# lupa300v3.net
KiCad netlist of a schematic drawn in EAGLE
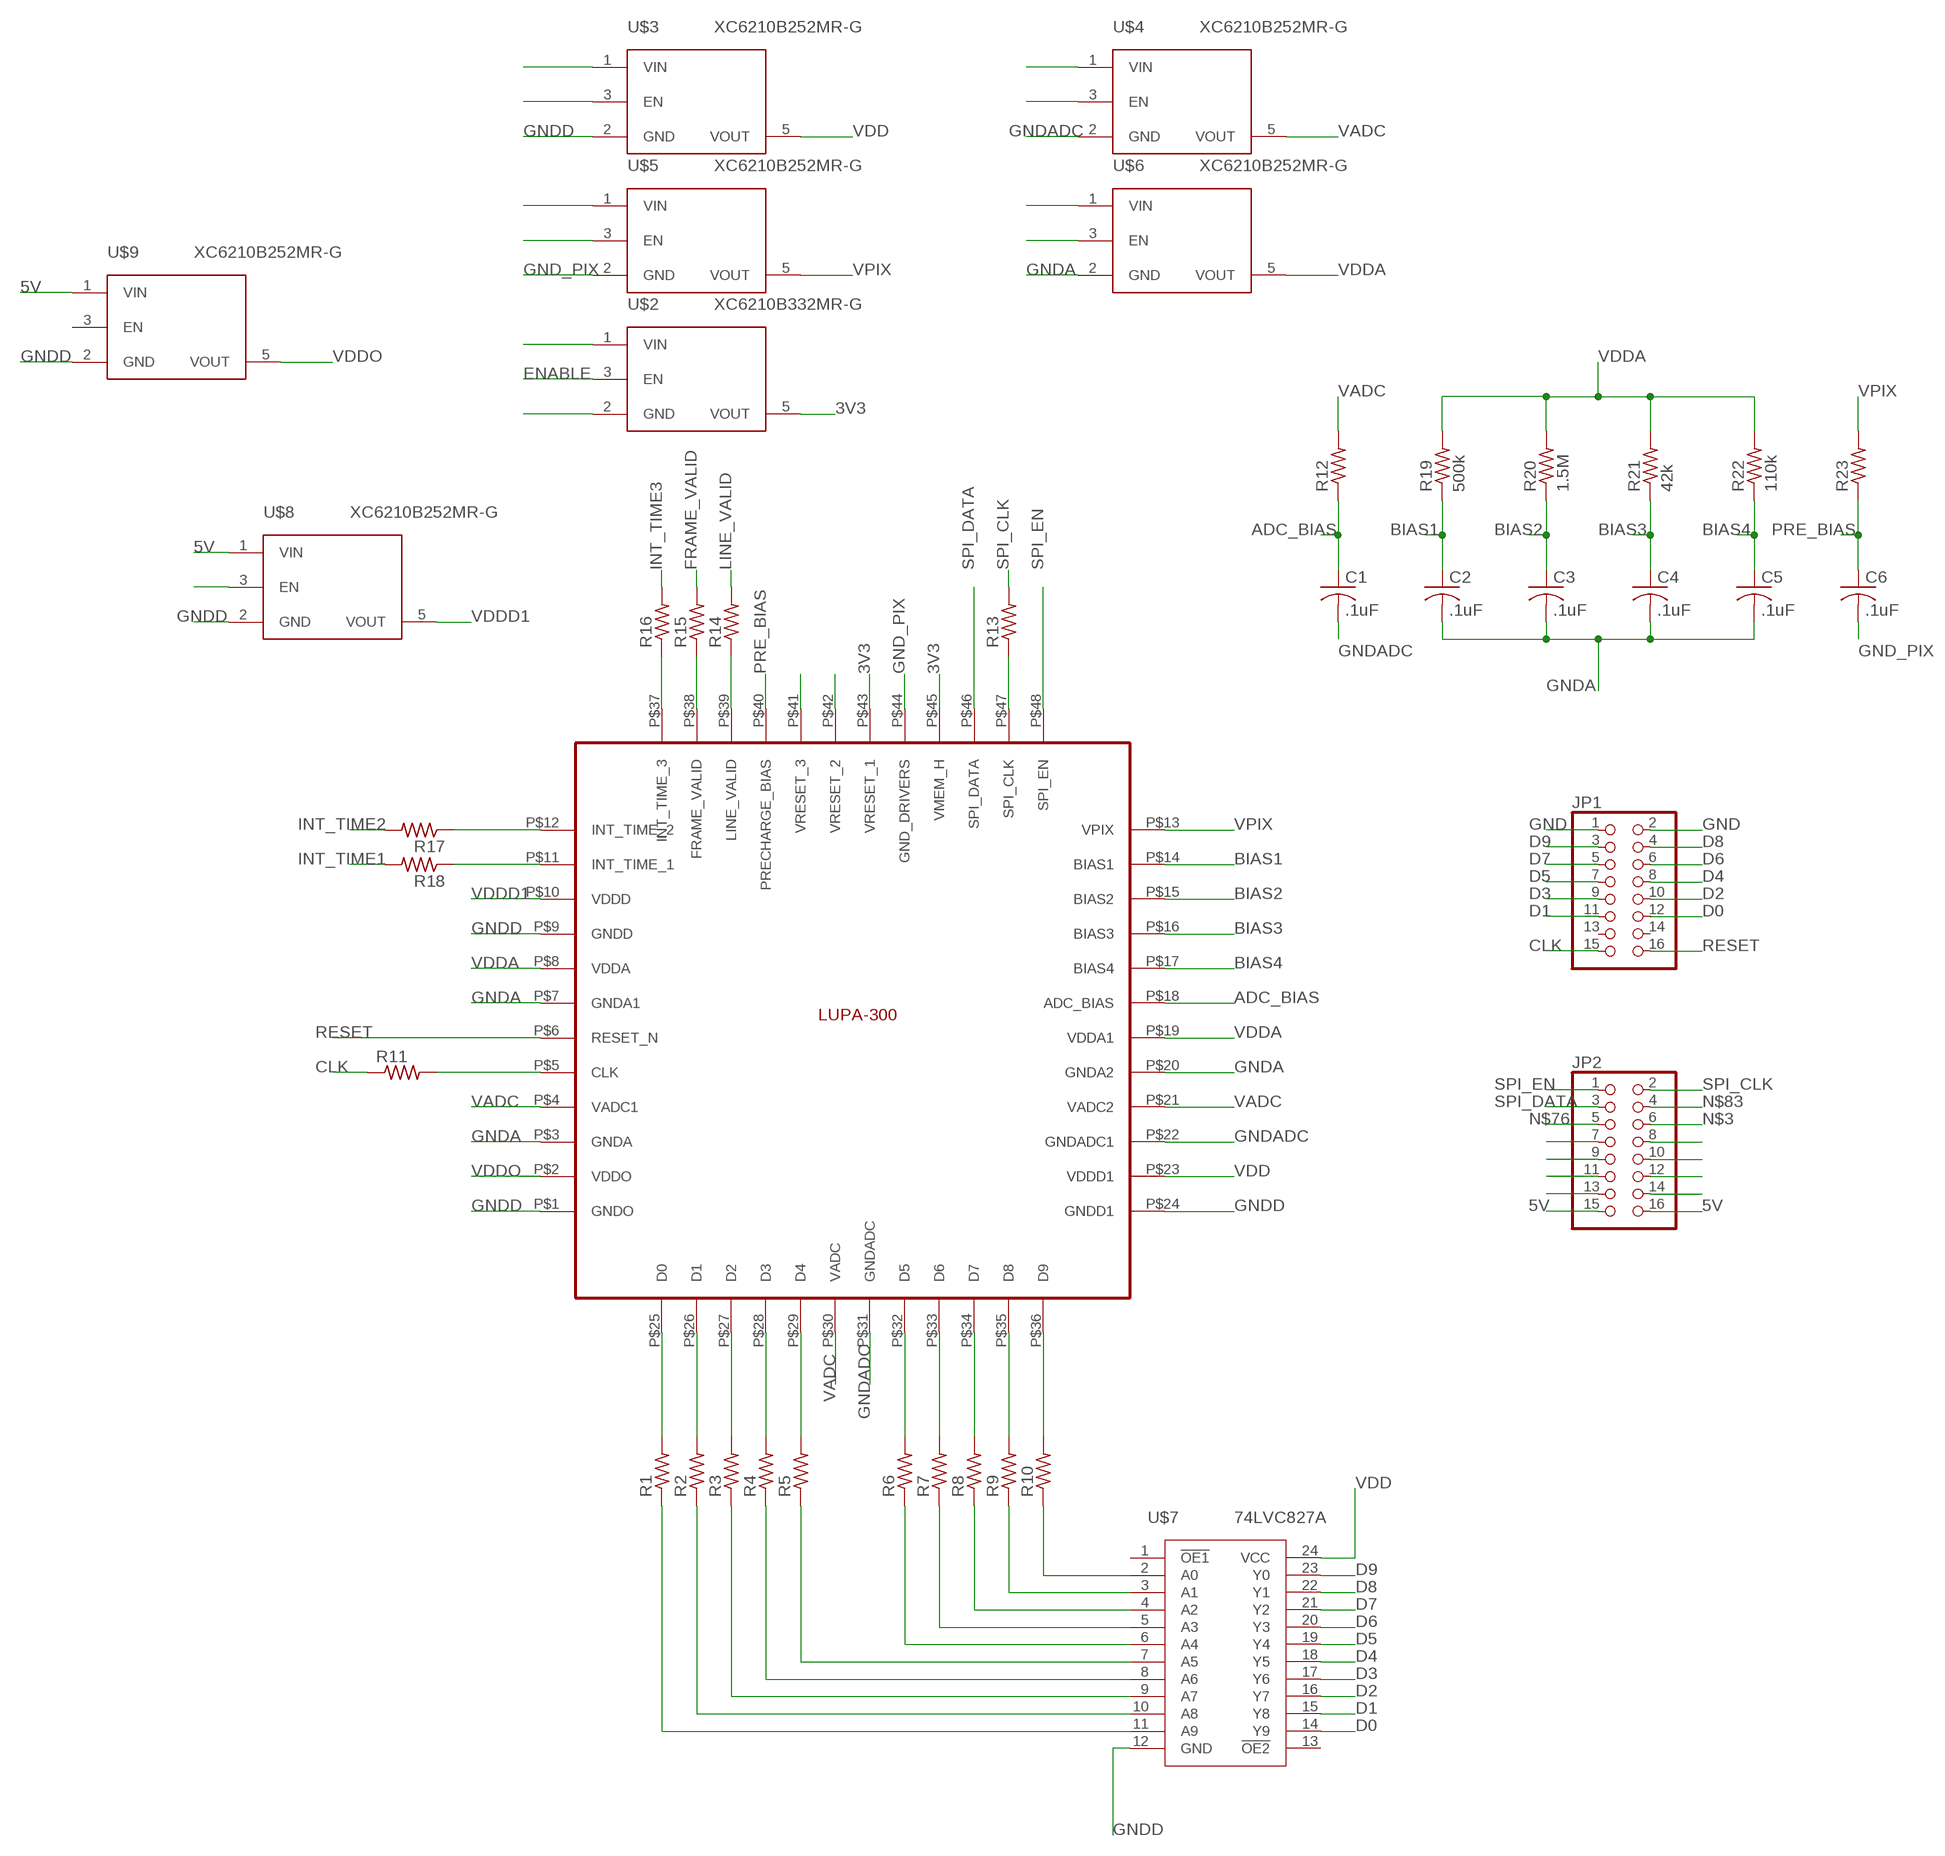
[diagram p0: schematic, sheet 1]

(export (version "E")
  (design (tool "Eeschema 10.0.6"))
  (components
    (comp (ref "C1")
      (value ".1uF")
      (footprint "eagle-import:C0603K")
      (libsource (lib "eagle-import") (part "C-USC0603K"))
    )
    (comp (ref "C2")
      (value ".1uF")
      (footprint "eagle-import:C0603K")
      (libsource (lib "eagle-import") (part "C-USC0603K"))
    )
    (comp (ref "C3")
      (value ".1uF")
      (footprint "eagle-import:C0603K")
      (libsource (lib "eagle-import") (part "C-USC0603K"))
    )
    (comp (ref "C4")
      (value ".1uF")
      (footprint "eagle-import:C0603K")
      (libsource (lib "eagle-import") (part "C-USC0603K"))
    )
    (comp (ref "C5")
      (value ".1uF")
      (footprint "eagle-import:C0603K")
      (libsource (lib "eagle-import") (part "C-USC0603K"))
    )
    (comp (ref "C6")
      (value ".1uF")
      (footprint "eagle-import:C0603K")
      (libsource (lib "eagle-import") (part "C-USC0603K"))
    )
    (comp (ref "JP1")
      (value "PINHD-2X8")
      (footprint "eagle-import:2X08")
      (libsource (lib "eagle-import") (part "PINHD-2X8"))
    )
    (comp (ref "JP2")
      (value "PINHD-2X8")
      (footprint "eagle-import:2X08")
      (libsource (lib "eagle-import") (part "PINHD-2X8"))
    )
    (comp (ref "R1")
      (value "R-US_R0603")
      (footprint "eagle-import:R0603")
      (libsource (lib "eagle-import") (part "R-US_R0603"))
    )
    (comp (ref "R2")
      (value "R-US_R0603")
      (footprint "eagle-import:R0603")
      (libsource (lib "eagle-import") (part "R-US_R0603"))
    )
    (comp (ref "R3")
      (value "R-US_R0603")
      (footprint "eagle-import:R0603")
      (libsource (lib "eagle-import") (part "R-US_R0603"))
    )
    (comp (ref "R4")
      (value "R-US_R0603")
      (footprint "eagle-import:R0603")
      (libsource (lib "eagle-import") (part "R-US_R0603"))
    )
    (comp (ref "R5")
      (value "R-US_R0603")
      (footprint "eagle-import:R0603")
      (libsource (lib "eagle-import") (part "R-US_R0603"))
    )
    (comp (ref "R6")
      (value "R-US_R0603")
      (footprint "eagle-import:R0603")
      (libsource (lib "eagle-import") (part "R-US_R0603"))
    )
    (comp (ref "R7")
      (value "R-US_R0603")
      (footprint "eagle-import:R0603")
      (libsource (lib "eagle-import") (part "R-US_R0603"))
    )
    (comp (ref "R8")
      (value "R-US_R0603")
      (footprint "eagle-import:R0603")
      (libsource (lib "eagle-import") (part "R-US_R0603"))
    )
    (comp (ref "R9")
      (value "R-US_R0603")
      (footprint "eagle-import:R0603")
      (libsource (lib "eagle-import") (part "R-US_R0603"))
    )
    (comp (ref "R10")
      (value "R-US_R0603")
      (footprint "eagle-import:R0603")
      (libsource (lib "eagle-import") (part "R-US_R0603"))
    )
    (comp (ref "R11")
      (value "R-US_R0603")
      (footprint "eagle-import:R0603")
      (libsource (lib "eagle-import") (part "R-US_R0603"))
    )
    (comp (ref "R12")
      (value "R-US_R0603")
      (footprint "eagle-import:R0603")
      (libsource (lib "eagle-import") (part "R-US_R0603"))
    )
    (comp (ref "R13")
      (value "R-US_R0603")
      (footprint "eagle-import:R0603")
      (libsource (lib "eagle-import") (part "R-US_R0603"))
    )
    (comp (ref "R14")
      (value "R-US_R0603")
      (footprint "eagle-import:R0603")
      (libsource (lib "eagle-import") (part "R-US_R0603"))
    )
    (comp (ref "R15")
      (value "R-US_R0603")
      (footprint "eagle-import:R0603")
      (libsource (lib "eagle-import") (part "R-US_R0603"))
    )
    (comp (ref "R16")
      (value "R-US_R0603")
      (footprint "eagle-import:R0603")
      (libsource (lib "eagle-import") (part "R-US_R0603"))
    )
    (comp (ref "R17")
      (value "R-US_R0603")
      (footprint "eagle-import:R0603")
      (libsource (lib "eagle-import") (part "R-US_R0603"))
    )
    (comp (ref "R18")
      (value "R-US_R0603")
      (footprint "eagle-import:R0603")
      (libsource (lib "eagle-import") (part "R-US_R0603"))
    )
    (comp (ref "R19")
      (value "500k")
      (footprint "eagle-import:R0603")
      (libsource (lib "eagle-import") (part "R-US_R0603"))
    )
    (comp (ref "R20")
      (value "1.5M")
      (footprint "eagle-import:R0603")
      (libsource (lib "eagle-import") (part "R-US_R0603"))
    )
    (comp (ref "R21")
      (value "42k")
      (footprint "eagle-import:R0603")
      (libsource (lib "eagle-import") (part "R-US_R0603"))
    )
    (comp (ref "R22")
      (value "110k")
      (footprint "eagle-import:R0603")
      (libsource (lib "eagle-import") (part "R-US_R0603"))
    )
    (comp (ref "R23")
      (value "R-US_R0603")
      (footprint "eagle-import:R0603")
      (libsource (lib "eagle-import") (part "R-US_R0603"))
    )
    (comp (ref "U$1")
      (value "LUPA300")
      (footprint "eagle-import:LUPA300")
      (libsource (lib "eagle-import") (part "LUPA300"))
    )
    (comp (ref "U$2")
      (value "XC6210B332MR-G")
      (footprint "eagle-import:SOT25")
      (libsource (lib "eagle-import") (part "XC6210B332MR-G"))
    )
    (comp (ref "U$3")
      (value "XC6210B252MR-G")
      (footprint "eagle-import:SOT25")
      (libsource (lib "eagle-import") (part "XC6210B252MR-G"))
    )
    (comp (ref "U$4")
      (value "XC6210B252MR-G")
      (footprint "eagle-import:SOT25")
      (libsource (lib "eagle-import") (part "XC6210B252MR-G"))
    )
    (comp (ref "U$5")
      (value "XC6210B252MR-G")
      (footprint "eagle-import:SOT25")
      (libsource (lib "eagle-import") (part "XC6210B252MR-G"))
    )
    (comp (ref "U$6")
      (value "XC6210B252MR-G")
      (footprint "eagle-import:SOT25")
      (libsource (lib "eagle-import") (part "XC6210B252MR-G"))
    )
    (comp (ref "U$7")
      (value "74LVC827A")
      (footprint "eagle-import:TSSOP24")
      (libsource (lib "eagle-import") (part "74LVC827A"))
    )
    (comp (ref "U$8")
      (value "XC6210B252MR-G")
      (footprint "eagle-import:SOT25")
      (libsource (lib "eagle-import") (part "XC6210B252MR-G"))
    )
    (comp (ref "U$9")
      (value "XC6210B252MR-G")
      (footprint "eagle-import:SOT25")
      (libsource (lib "eagle-import") (part "XC6210B252MR-G"))
    )
  )
  (nets
    (net (code "1") (name "/3V3") (class "Default")
      (node (ref "U$1") (pin "P$43") (pinfunction "VRESET_1_P$43") (pintype "bidirectional"))
      (node (ref "U$1") (pin "P$45") (pinfunction "VMEM_H_P$45") (pintype "bidirectional"))
      (node (ref "U$2") (pin "5") (pinfunction "VOUT_5") (pintype "bidirectional"))
    )
    (net (code "2") (name "/5V") (class "Default")
      (node (ref "JP2") (pin "15") (pinfunction "15_15") (pintype "passive"))
      (node (ref "JP2") (pin "16") (pinfunction "16_16") (pintype "passive"))
      (node (ref "U$2") (pin "1") (pinfunction "VIN_1") (pintype "bidirectional"))
      (node (ref "U$3") (pin "1") (pinfunction "VIN_1") (pintype "bidirectional"))
      (node (ref "U$4") (pin "1") (pinfunction "VIN_1") (pintype "bidirectional"))
      (node (ref "U$5") (pin "1") (pinfunction "VIN_1") (pintype "bidirectional"))
      (node (ref "U$6") (pin "1") (pinfunction "VIN_1") (pintype "bidirectional"))
      (node (ref "U$8") (pin "1") (pinfunction "VIN_1") (pintype "bidirectional"))
      (node (ref "U$9") (pin "1") (pinfunction "VIN_1") (pintype "bidirectional"))
    )
    (net (code "3") (name "/ADC_BIAS") (class "Default")
      (node (ref "C1") (pin "1") (pinfunction "1_1") (pintype "passive"))
      (node (ref "R12") (pin "1") (pinfunction "1_1") (pintype "passive"))
      (node (ref "U$1") (pin "P$18") (pinfunction "ADC_BIAS_P$18") (pintype "bidirectional"))
    )
    (net (code "4") (name "/BIAS1") (class "Default")
      (node (ref "C2") (pin "1") (pinfunction "1_1") (pintype "passive"))
      (node (ref "R19") (pin "1") (pinfunction "1_1") (pintype "passive"))
      (node (ref "U$1") (pin "P$14") (pinfunction "BIAS1_P$14") (pintype "bidirectional"))
    )
    (net (code "5") (name "/BIAS2") (class "Default")
      (node (ref "C3") (pin "1") (pinfunction "1_1") (pintype "passive"))
      (node (ref "R20") (pin "1") (pinfunction "1_1") (pintype "passive"))
      (node (ref "U$1") (pin "P$15") (pinfunction "BIAS2_P$15") (pintype "bidirectional"))
    )
    (net (code "6") (name "/BIAS3") (class "Default")
      (node (ref "C4") (pin "1") (pinfunction "1_1") (pintype "passive"))
      (node (ref "R21") (pin "1") (pinfunction "1_1") (pintype "passive"))
      (node (ref "U$1") (pin "P$16") (pinfunction "BIAS3_P$16") (pintype "bidirectional"))
    )
    (net (code "7") (name "/BIAS4") (class "Default")
      (node (ref "C5") (pin "1") (pinfunction "1_1") (pintype "passive"))
      (node (ref "R22") (pin "1") (pinfunction "1_1") (pintype "passive"))
      (node (ref "U$1") (pin "P$17") (pinfunction "BIAS4_P$17") (pintype "bidirectional"))
    )
    (net (code "8") (name "/CLK") (class "Default")
      (node (ref "JP1") (pin "15") (pinfunction "15_15") (pintype "passive"))
      (node (ref "R11") (pin "1") (pinfunction "1_1") (pintype "passive"))
    )
    (net (code "9") (name "/D0") (class "Default")
      (node (ref "JP1") (pin "12") (pinfunction "12_12") (pintype "passive"))
      (node (ref "U$7") (pin "14") (pinfunction "Y9_14") (pintype "bidirectional"))
    )
    (net (code "10") (name "/D1") (class "Default")
      (node (ref "JP1") (pin "11") (pinfunction "11_11") (pintype "passive"))
      (node (ref "U$7") (pin "15") (pinfunction "Y8_15") (pintype "bidirectional"))
    )
    (net (code "11") (name "/D2") (class "Default")
      (node (ref "JP1") (pin "10") (pinfunction "10_10") (pintype "passive"))
      (node (ref "U$7") (pin "16") (pinfunction "Y7_16") (pintype "bidirectional"))
    )
    (net (code "12") (name "/D3") (class "Default")
      (node (ref "JP1") (pin "9") (pinfunction "9_9") (pintype "passive"))
      (node (ref "U$7") (pin "17") (pinfunction "Y6_17") (pintype "bidirectional"))
    )
    (net (code "13") (name "/D4") (class "Default")
      (node (ref "JP1") (pin "8") (pinfunction "8_8") (pintype "passive"))
      (node (ref "U$7") (pin "18") (pinfunction "Y5_18") (pintype "bidirectional"))
    )
    (net (code "14") (name "/D5") (class "Default")
      (node (ref "JP1") (pin "7") (pinfunction "7_7") (pintype "passive"))
      (node (ref "U$7") (pin "19") (pinfunction "Y4_19") (pintype "bidirectional"))
    )
    (net (code "15") (name "/D6") (class "Default")
      (node (ref "JP1") (pin "6") (pinfunction "6_6") (pintype "passive"))
      (node (ref "U$7") (pin "20") (pinfunction "Y3_20") (pintype "bidirectional"))
    )
    (net (code "16") (name "/D7") (class "Default")
      (node (ref "JP1") (pin "5") (pinfunction "5_5") (pintype "passive"))
      (node (ref "U$7") (pin "21") (pinfunction "Y2_21") (pintype "bidirectional"))
    )
    (net (code "17") (name "/D8") (class "Default")
      (node (ref "JP1") (pin "4") (pinfunction "4_4") (pintype "passive"))
      (node (ref "U$7") (pin "22") (pinfunction "Y1_22") (pintype "bidirectional"))
    )
    (net (code "18") (name "/D9") (class "Default")
      (node (ref "JP1") (pin "3") (pinfunction "3_3") (pintype "passive"))
      (node (ref "U$7") (pin "23") (pinfunction "Y0_23") (pintype "bidirectional"))
    )
    (net (code "19") (name "/ENABLE") (class "Default")
      (node (ref "U$2") (pin "3") (pinfunction "EN_3") (pintype "bidirectional"))
      (node (ref "U$3") (pin "3") (pinfunction "EN_3") (pintype "bidirectional"))
      (node (ref "U$4") (pin "3") (pinfunction "EN_3") (pintype "bidirectional"))
      (node (ref "U$5") (pin "3") (pinfunction "EN_3") (pintype "bidirectional"))
      (node (ref "U$6") (pin "3") (pinfunction "EN_3") (pintype "bidirectional"))
    )
    (net (code "20") (name "/FRAME_VALID") (class "Default")
      (node (ref "R15") (pin "2") (pinfunction "2_2") (pintype "passive"))
    )
    (net (code "21") (name "/GND") (class "Default")
      (node (ref "JP1") (pin "1") (pinfunction "1_1") (pintype "passive"))
      (node (ref "JP1") (pin "2") (pinfunction "2_2") (pintype "passive"))
    )
    (net (code "22") (name "/GNDA") (class "Default")
      (node (ref "C2") (pin "2") (pinfunction "2_2") (pintype "passive"))
      (node (ref "C3") (pin "2") (pinfunction "2_2") (pintype "passive"))
      (node (ref "C4") (pin "2") (pinfunction "2_2") (pintype "passive"))
      (node (ref "C5") (pin "2") (pinfunction "2_2") (pintype "passive"))
      (node (ref "U$1") (pin "P$20") (pinfunction "GNDA2_P$20") (pintype "bidirectional"))
      (node (ref "U$1") (pin "P$3") (pinfunction "GNDA_P$3") (pintype "bidirectional"))
      (node (ref "U$1") (pin "P$7") (pinfunction "GNDA1_P$7") (pintype "bidirectional"))
      (node (ref "U$6") (pin "2") (pinfunction "GND_2") (pintype "bidirectional"))
    )
    (net (code "23") (name "/GNDADC") (class "Default")
      (node (ref "C1") (pin "2") (pinfunction "2_2") (pintype "passive"))
      (node (ref "U$1") (pin "P$22") (pinfunction "GNDADC1_P$22") (pintype "bidirectional"))
      (node (ref "U$1") (pin "P$31") (pinfunction "GNDADC_P$31") (pintype "bidirectional"))
      (node (ref "U$4") (pin "2") (pinfunction "GND_2") (pintype "bidirectional"))
    )
    (net (code "24") (name "/GNDD") (class "Default")
      (node (ref "U$1") (pin "P$1") (pinfunction "GNDO_P$1") (pintype "bidirectional"))
      (node (ref "U$1") (pin "P$24") (pinfunction "GNDD1_P$24") (pintype "bidirectional"))
      (node (ref "U$1") (pin "P$9") (pinfunction "GNDD_P$9") (pintype "bidirectional"))
      (node (ref "U$3") (pin "2") (pinfunction "GND_2") (pintype "bidirectional"))
      (node (ref "U$7") (pin "12") (pinfunction "GND_12") (pintype "bidirectional"))
      (node (ref "U$8") (pin "2") (pinfunction "GND_2") (pintype "bidirectional"))
      (node (ref "U$9") (pin "2") (pinfunction "GND_2") (pintype "bidirectional"))
    )
    (net (code "25") (name "/GND_PIX") (class "Default")
      (node (ref "C6") (pin "2") (pinfunction "2_2") (pintype "passive"))
      (node (ref "U$1") (pin "P$44") (pinfunction "GND_DRIVERS_P$44") (pintype "bidirectional"))
      (node (ref "U$5") (pin "2") (pinfunction "GND_2") (pintype "bidirectional"))
    )
    (net (code "26") (name "/INT_TIME1") (class "Default")
      (node (ref "R18") (pin "2") (pinfunction "2_2") (pintype "passive"))
    )
    (net (code "27") (name "/INT_TIME2") (class "Default")
      (node (ref "R17") (pin "2") (pinfunction "2_2") (pintype "passive"))
    )
    (net (code "28") (name "/INT_TIME3") (class "Default")
      (node (ref "R16") (pin "2") (pinfunction "2_2") (pintype "passive"))
    )
    (net (code "29") (name "/LINE_VALID") (class "Default")
      (node (ref "R14") (pin "2") (pinfunction "2_2") (pintype "passive"))
    )
    (net (code "30") (name "/N$3") (class "Default")
      (node (ref "JP2") (pin "6") (pinfunction "6_6") (pintype "passive"))
    )
    (net (code "31") (name "/N$76") (class "Default")
      (node (ref "JP2") (pin "5") (pinfunction "5_5") (pintype "passive"))
    )
    (net (code "32") (name "/N$83") (class "Default")
      (node (ref "JP2") (pin "4") (pinfunction "4_4") (pintype "passive"))
    )
    (net (code "33") (name "/PRE_BIAS") (class "Default")
      (node (ref "C6") (pin "1") (pinfunction "1_1") (pintype "passive"))
      (node (ref "R23") (pin "1") (pinfunction "1_1") (pintype "passive"))
      (node (ref "U$1") (pin "P$40") (pinfunction "PRECHARGE_BIAS_P$40") (pintype "bidirectional"))
    )
    (net (code "34") (name "/RESET") (class "Default")
      (node (ref "JP1") (pin "16") (pinfunction "16_16") (pintype "passive"))
      (node (ref "U$1") (pin "P$6") (pinfunction "RESET_N_P$6") (pintype "bidirectional"))
    )
    (net (code "35") (name "/SPI_CLK") (class "Default")
      (node (ref "JP2") (pin "2") (pinfunction "2_2") (pintype "passive"))
      (node (ref "R13") (pin "2") (pinfunction "2_2") (pintype "passive"))
    )
    (net (code "36") (name "/SPI_DATA") (class "Default")
      (node (ref "JP2") (pin "3") (pinfunction "3_3") (pintype "passive"))
      (node (ref "U$1") (pin "P$46") (pinfunction "SPI_DATA_P$46") (pintype "bidirectional"))
    )
    (net (code "37") (name "/SPI_EN") (class "Default")
      (node (ref "JP2") (pin "1") (pinfunction "1_1") (pintype "passive"))
      (node (ref "U$1") (pin "P$48") (pinfunction "SPI_EN_P$48") (pintype "bidirectional"))
    )
    (net (code "38") (name "/VADC") (class "Default")
      (node (ref "R12") (pin "2") (pinfunction "2_2") (pintype "passive"))
      (node (ref "U$1") (pin "P$21") (pinfunction "VADC2_P$21") (pintype "bidirectional"))
      (node (ref "U$1") (pin "P$30") (pinfunction "VADC_P$30") (pintype "bidirectional"))
      (node (ref "U$1") (pin "P$4") (pinfunction "VADC1_P$4") (pintype "bidirectional"))
      (node (ref "U$4") (pin "5") (pinfunction "VOUT_5") (pintype "bidirectional"))
    )
    (net (code "39") (name "/VDD") (class "Default")
      (node (ref "U$1") (pin "P$23") (pinfunction "VDDD1_P$23") (pintype "bidirectional"))
      (node (ref "U$3") (pin "5") (pinfunction "VOUT_5") (pintype "bidirectional"))
      (node (ref "U$7") (pin "24") (pinfunction "VCC_24") (pintype "bidirectional"))
    )
    (net (code "40") (name "/VDDA") (class "Default")
      (node (ref "R19") (pin "2") (pinfunction "2_2") (pintype "passive"))
      (node (ref "R20") (pin "2") (pinfunction "2_2") (pintype "passive"))
      (node (ref "R21") (pin "2") (pinfunction "2_2") (pintype "passive"))
      (node (ref "R22") (pin "2") (pinfunction "2_2") (pintype "passive"))
      (node (ref "U$1") (pin "P$19") (pinfunction "VDDA1_P$19") (pintype "bidirectional"))
      (node (ref "U$1") (pin "P$8") (pinfunction "VDDA_P$8") (pintype "bidirectional"))
      (node (ref "U$6") (pin "5") (pinfunction "VOUT_5") (pintype "bidirectional"))
    )
    (net (code "41") (name "/VDDD1") (class "Default")
      (node (ref "U$1") (pin "P$10") (pinfunction "VDDD_P$10") (pintype "bidirectional"))
      (node (ref "U$8") (pin "5") (pinfunction "VOUT_5") (pintype "bidirectional"))
    )
    (net (code "42") (name "/VDDO") (class "Default")
      (node (ref "U$1") (pin "P$2") (pinfunction "VDDO_P$2") (pintype "bidirectional"))
      (node (ref "U$9") (pin "5") (pinfunction "VOUT_5") (pintype "bidirectional"))
    )
    (net (code "43") (name "/VPIX") (class "Default")
      (node (ref "R23") (pin "2") (pinfunction "2_2") (pintype "passive"))
      (node (ref "U$1") (pin "P$13") (pinfunction "VPIX_P$13") (pintype "bidirectional"))
      (node (ref "U$5") (pin "5") (pinfunction "VOUT_5") (pintype "bidirectional"))
    )
    (net (code "44") (name "Net-(U$1-CLK)") (class "Default")
      (node (ref "R11") (pin "2") (pinfunction "2_2") (pintype "passive"))
      (node (ref "U$1") (pin "P$5") (pinfunction "CLK_P$5") (pintype "bidirectional"))
    )
    (net (code "45") (name "Net-(U$1-D0)") (class "Default")
      (node (ref "R1") (pin "2") (pinfunction "2_2") (pintype "passive"))
      (node (ref "U$1") (pin "P$25") (pinfunction "D0_P$25") (pintype "bidirectional"))
    )
    (net (code "46") (name "Net-(U$1-D1)") (class "Default")
      (node (ref "R2") (pin "2") (pinfunction "2_2") (pintype "passive"))
      (node (ref "U$1") (pin "P$26") (pinfunction "D1_P$26") (pintype "bidirectional"))
    )
    (net (code "47") (name "Net-(U$1-D2)") (class "Default")
      (node (ref "R3") (pin "2") (pinfunction "2_2") (pintype "passive"))
      (node (ref "U$1") (pin "P$27") (pinfunction "D2_P$27") (pintype "bidirectional"))
    )
    (net (code "48") (name "Net-(U$1-D3)") (class "Default")
      (node (ref "R4") (pin "2") (pinfunction "2_2") (pintype "passive"))
      (node (ref "U$1") (pin "P$28") (pinfunction "D3_P$28") (pintype "bidirectional"))
    )
    (net (code "49") (name "Net-(U$1-D4)") (class "Default")
      (node (ref "R5") (pin "2") (pinfunction "2_2") (pintype "passive"))
      (node (ref "U$1") (pin "P$29") (pinfunction "D4_P$29") (pintype "bidirectional"))
    )
    (net (code "50") (name "Net-(U$1-D5)") (class "Default")
      (node (ref "R6") (pin "2") (pinfunction "2_2") (pintype "passive"))
      (node (ref "U$1") (pin "P$32") (pinfunction "D5_P$32") (pintype "bidirectional"))
    )
    (net (code "51") (name "Net-(U$1-D6)") (class "Default")
      (node (ref "R7") (pin "2") (pinfunction "2_2") (pintype "passive"))
      (node (ref "U$1") (pin "P$33") (pinfunction "D6_P$33") (pintype "bidirectional"))
    )
    (net (code "52") (name "Net-(U$1-D7)") (class "Default")
      (node (ref "R8") (pin "2") (pinfunction "2_2") (pintype "passive"))
      (node (ref "U$1") (pin "P$34") (pinfunction "D7_P$34") (pintype "bidirectional"))
    )
    (net (code "53") (name "Net-(U$1-D8)") (class "Default")
      (node (ref "R9") (pin "2") (pinfunction "2_2") (pintype "passive"))
      (node (ref "U$1") (pin "P$35") (pinfunction "D8_P$35") (pintype "bidirectional"))
    )
    (net (code "54") (name "Net-(U$1-D9)") (class "Default")
      (node (ref "R10") (pin "2") (pinfunction "2_2") (pintype "passive"))
      (node (ref "U$1") (pin "P$36") (pinfunction "D9_P$36") (pintype "bidirectional"))
    )
    (net (code "55") (name "Net-(U$1-FRAME_VALID)") (class "Default")
      (node (ref "R15") (pin "1") (pinfunction "1_1") (pintype "passive"))
      (node (ref "U$1") (pin "P$38") (pinfunction "FRAME_VALID_P$38") (pintype "bidirectional"))
    )
    (net (code "56") (name "Net-(U$1-INT_TIME_1)") (class "Default")
      (node (ref "R18") (pin "1") (pinfunction "1_1") (pintype "passive"))
      (node (ref "U$1") (pin "P$11") (pinfunction "INT_TIME_1_P$11") (pintype "bidirectional"))
    )
    (net (code "57") (name "Net-(U$1-INT_TIME_2)") (class "Default")
      (node (ref "R17") (pin "1") (pinfunction "1_1") (pintype "passive"))
      (node (ref "U$1") (pin "P$12") (pinfunction "INT_TIME_2_P$12") (pintype "bidirectional"))
    )
    (net (code "58") (name "Net-(U$1-INT_TIME_3)") (class "Default")
      (node (ref "R16") (pin "1") (pinfunction "1_1") (pintype "passive"))
      (node (ref "U$1") (pin "P$37") (pinfunction "INT_TIME_3_P$37") (pintype "bidirectional"))
    )
    (net (code "59") (name "Net-(U$1-LINE_VALID)") (class "Default")
      (node (ref "R14") (pin "1") (pinfunction "1_1") (pintype "passive"))
      (node (ref "U$1") (pin "P$39") (pinfunction "LINE_VALID_P$39") (pintype "bidirectional"))
    )
    (net (code "60") (name "Net-(U$1-SPI_CLK)") (class "Default")
      (node (ref "R13") (pin "1") (pinfunction "1_1") (pintype "passive"))
      (node (ref "U$1") (pin "P$47") (pinfunction "SPI_CLK_P$47") (pintype "bidirectional"))
    )
    (net (code "61") (name "Net-(U$7-A0)") (class "Default")
      (node (ref "R10") (pin "1") (pinfunction "1_1") (pintype "passive"))
      (node (ref "U$7") (pin "2") (pinfunction "A0_2") (pintype "bidirectional"))
    )
    (net (code "62") (name "Net-(U$7-A1)") (class "Default")
      (node (ref "R9") (pin "1") (pinfunction "1_1") (pintype "passive"))
      (node (ref "U$7") (pin "3") (pinfunction "A1_3") (pintype "bidirectional"))
    )
    (net (code "63") (name "Net-(U$7-A2)") (class "Default")
      (node (ref "R8") (pin "1") (pinfunction "1_1") (pintype "passive"))
      (node (ref "U$7") (pin "4") (pinfunction "A2_4") (pintype "bidirectional"))
    )
    (net (code "64") (name "Net-(U$7-A3)") (class "Default")
      (node (ref "R7") (pin "1") (pinfunction "1_1") (pintype "passive"))
      (node (ref "U$7") (pin "5") (pinfunction "A3_5") (pintype "bidirectional"))
    )
    (net (code "65") (name "Net-(U$7-A4)") (class "Default")
      (node (ref "R6") (pin "1") (pinfunction "1_1") (pintype "passive"))
      (node (ref "U$7") (pin "6") (pinfunction "A4_6") (pintype "bidirectional"))
    )
    (net (code "66") (name "Net-(U$7-A5)") (class "Default")
      (node (ref "R5") (pin "1") (pinfunction "1_1") (pintype "passive"))
      (node (ref "U$7") (pin "7") (pinfunction "A5_7") (pintype "bidirectional"))
    )
    (net (code "67") (name "Net-(U$7-A6)") (class "Default")
      (node (ref "R4") (pin "1") (pinfunction "1_1") (pintype "passive"))
      (node (ref "U$7") (pin "8") (pinfunction "A6_8") (pintype "bidirectional"))
    )
    (net (code "68") (name "Net-(U$7-A7)") (class "Default")
      (node (ref "R3") (pin "1") (pinfunction "1_1") (pintype "passive"))
      (node (ref "U$7") (pin "9") (pinfunction "A7_9") (pintype "bidirectional"))
    )
    (net (code "69") (name "Net-(U$7-A8)") (class "Default")
      (node (ref "R2") (pin "1") (pinfunction "1_1") (pintype "passive"))
      (node (ref "U$7") (pin "10") (pinfunction "A8_10") (pintype "bidirectional"))
    )
    (net (code "70") (name "Net-(U$7-A9)") (class "Default")
      (node (ref "R1") (pin "1") (pinfunction "1_1") (pintype "passive"))
      (node (ref "U$7") (pin "11") (pinfunction "A9_11") (pintype "bidirectional"))
    )
    (net (code "71") (name "unconnected-(JP1-Pad13)") (class "Default")
      (node (ref "JP1") (pin "13") (pinfunction "13_13") (pintype "passive"))
    )
    (net (code "72") (name "unconnected-(JP1-Pad14)") (class "Default")
      (node (ref "JP1") (pin "14") (pinfunction "14_14") (pintype "passive"))
    )
    (net (code "73") (name "unconnected-(JP2-Pad7)") (class "Default")
      (node (ref "JP2") (pin "7") (pinfunction "7_7") (pintype "passive"))
    )
    (net (code "74") (name "unconnected-(JP2-Pad8)") (class "Default")
      (node (ref "JP2") (pin "8") (pinfunction "8_8") (pintype "passive"))
    )
    (net (code "75") (name "unconnected-(JP2-Pad9)") (class "Default")
      (node (ref "JP2") (pin "9") (pinfunction "9_9") (pintype "passive"))
    )
    (net (code "76") (name "unconnected-(JP2-Pad10)") (class "Default")
      (node (ref "JP2") (pin "10") (pinfunction "10_10") (pintype "passive"))
    )
    (net (code "77") (name "unconnected-(JP2-Pad11)") (class "Default")
      (node (ref "JP2") (pin "11") (pinfunction "11_11") (pintype "passive"))
    )
    (net (code "78") (name "unconnected-(JP2-Pad12)") (class "Default")
      (node (ref "JP2") (pin "12") (pinfunction "12_12") (pintype "passive"))
    )
    (net (code "79") (name "unconnected-(JP2-Pad13)") (class "Default")
      (node (ref "JP2") (pin "13") (pinfunction "13_13") (pintype "passive"))
    )
    (net (code "80") (name "unconnected-(JP2-Pad14)") (class "Default")
      (node (ref "JP2") (pin "14") (pinfunction "14_14") (pintype "passive"))
    )
    (net (code "81") (name "unconnected-(U$1-VRESET_2-PadP$42)") (class "Default")
      (node (ref "U$1") (pin "P$42") (pinfunction "VRESET_2_P$42") (pintype "bidirectional"))
    )
    (net (code "82") (name "unconnected-(U$1-VRESET_3-PadP$41)") (class "Default")
      (node (ref "U$1") (pin "P$41") (pinfunction "VRESET_3_P$41") (pintype "bidirectional"))
    )
    (net (code "83") (name "unconnected-(U$2-GND-Pad2)") (class "Default")
      (node (ref "U$2") (pin "2") (pinfunction "GND_2") (pintype "bidirectional"))
    )
    (net (code "84") (name "unconnected-(U$7-~{OE1}-Pad1)") (class "Default")
      (node (ref "U$7") (pin "1") (pinfunction "~{OE1}_1") (pintype "bidirectional"))
    )
    (net (code "85") (name "unconnected-(U$7-~{OE2}-Pad13)") (class "Default")
      (node (ref "U$7") (pin "13") (pinfunction "~{OE2}_13") (pintype "bidirectional"))
    )
    (net (code "86") (name "unconnected-(U$8-EN-Pad3)") (class "Default")
      (node (ref "U$8") (pin "3") (pinfunction "EN_3") (pintype "bidirectional"))
    )
    (net (code "87") (name "unconnected-(U$9-EN-Pad3)") (class "Default")
      (node (ref "U$9") (pin "3") (pinfunction "EN_3") (pintype "bidirectional"))
    )
  )
)
